# DAC_Offset.net
KiCad netlist of a schematic drawn in Altium Designer
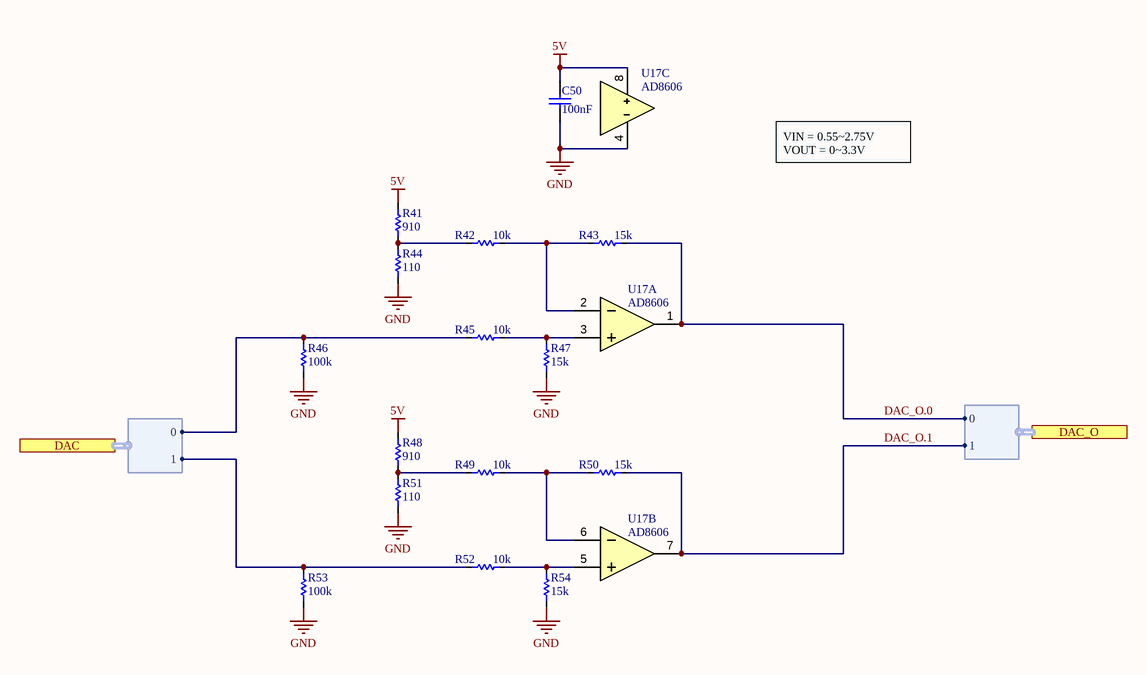
[diagram p0: DAC Offset.SchDoc]

(export (version "E")
  (design (tool "Eeschema 10.0.6"))
  (components
    (comp (ref "C50")
      (value "100nF")
      (footprint "CAP_CHIP_0603")
      (description "0603 Multilayer Ceramic Capacitors MLCC")
      (fields (field (name "TOLERANCE") "10%") (field (name "PARTNUMBER") "CC0603KRX7R9BB104"))
      (libsource (lib "Sainsbury Wellcome Centre") (part "Cap"))
    )
    (comp (ref "R41")
      (value "910")
      (footprint "RES_CHIP_0603")
      (description "100mW Thick Film Resistors 75V ±100ppm/℃ ±1% 0603 Chip Resistor")
      (fields (field (name "PARTNUMBER") "HPCR0603F910RK9") (field (name "TOLERANCE") "1%"))
      (libsource (lib "Sainsbury Wellcome Centre") (part "Res"))
    )
    (comp (ref "R42")
      (value "10k")
      (footprint "RES_CHIP_0603")
      (description "100mW Thick Film Resistors 75V ±100ppm/℃ ±1% 0603 Chip Resistor")
      (fields (field (name "PARTNUMBER") "0603WAF1002T5E") (field (name "TOLERANCE") "1%"))
      (libsource (lib "Sainsbury Wellcome Centre") (part "Res"))
    )
    (comp (ref "R43")
      (value "15k")
      (footprint "RES_CHIP_0603")
      (description "100mW Thick Film Resistors 75V ±100ppm/℃ ±1% 0603 Chip Resistor")
      (fields (field (name "PARTNUMBER") "0603WAF1502T5E") (field (name "TOLERANCE") "1%"))
      (libsource (lib "Sainsbury Wellcome Centre") (part "Res"))
    )
    (comp (ref "R44")
      (value "110")
      (footprint "RES_CHIP_0603")
      (description "100mW Thick Film Resistors 75V ±100ppm/℃ ±1% 0603 Chip Resistor")
      (fields (field (name "TOLERANCE") "1%") (field (name "PARTNUMBER") "RT0603BRD07110RL"))
      (libsource (lib "Sainsbury Wellcome Centre") (part "Res"))
    )
    (comp (ref "R45")
      (value "10k")
      (footprint "RES_CHIP_0603")
      (description "100mW Thick Film Resistors 75V ±100ppm/℃ ±1% 0603 Chip Resistor")
      (fields (field (name "PARTNUMBER") "0603WAF1002T5E") (field (name "TOLERANCE") "1%"))
      (libsource (lib "Sainsbury Wellcome Centre") (part "Res"))
    )
    (comp (ref "R46")
      (value "100k")
      (footprint "RES_CHIP_0603")
      (description "100mW Thick Film Resistors 75V ±100ppm/℃ ±1% 0603 Chip Resistor")
      (fields (field (name "PARTNUMBER") "0603WAF1003T5E") (field (name "TOLERANCE") "1%"))
      (libsource (lib "Sainsbury Wellcome Centre") (part "Res"))
    )
    (comp (ref "R47")
      (value "15k")
      (footprint "RES_CHIP_0603")
      (description "100mW Thick Film Resistors 75V ±100ppm/℃ ±1% 0603 Chip Resistor")
      (fields (field (name "PARTNUMBER") "0603WAF1502T5E") (field (name "TOLERANCE") "1%"))
      (libsource (lib "Sainsbury Wellcome Centre") (part "Res"))
    )
    (comp (ref "R48")
      (value "910")
      (footprint "RES_CHIP_0603")
      (description "100mW Thick Film Resistors 75V ±100ppm/℃ ±1% 0603 Chip Resistor")
      (fields (field (name "PARTNUMBER") "HPCR0603F910RK9") (field (name "TOLERANCE") "1%"))
      (libsource (lib "Sainsbury Wellcome Centre") (part "Res"))
    )
    (comp (ref "R49")
      (value "10k")
      (footprint "RES_CHIP_0603")
      (description "100mW Thick Film Resistors 75V ±100ppm/℃ ±1% 0603 Chip Resistor")
      (fields (field (name "PARTNUMBER") "0603WAF1002T5E") (field (name "TOLERANCE") "1%"))
      (libsource (lib "Sainsbury Wellcome Centre") (part "Res"))
    )
    (comp (ref "R50")
      (value "15k")
      (footprint "RES_CHIP_0603")
      (description "100mW Thick Film Resistors 75V ±100ppm/℃ ±1% 0603 Chip Resistor")
      (fields (field (name "PARTNUMBER") "0603WAF1502T5E") (field (name "TOLERANCE") "1%"))
      (libsource (lib "Sainsbury Wellcome Centre") (part "Res"))
    )
    (comp (ref "R51")
      (value "110")
      (footprint "RES_CHIP_0603")
      (description "100mW Thick Film Resistors 75V ±100ppm/℃ ±1% 0603 Chip Resistor")
      (fields (field (name "TOLERANCE") "1%") (field (name "PARTNUMBER") "RT0603BRD07110RL"))
      (libsource (lib "Sainsbury Wellcome Centre") (part "Res"))
    )
    (comp (ref "R52")
      (value "10k")
      (footprint "RES_CHIP_0603")
      (description "100mW Thick Film Resistors 75V ±100ppm/℃ ±1% 0603 Chip Resistor")
      (fields (field (name "PARTNUMBER") "0603WAF1002T5E") (field (name "TOLERANCE") "1%"))
      (libsource (lib "Sainsbury Wellcome Centre") (part "Res"))
    )
    (comp (ref "R53")
      (value "100k")
      (footprint "RES_CHIP_0603")
      (description "100mW Thick Film Resistors 75V ±100ppm/℃ ±1% 0603 Chip Resistor")
      (fields (field (name "PARTNUMBER") "0603WAF1003T5E") (field (name "TOLERANCE") "1%"))
      (libsource (lib "Sainsbury Wellcome Centre") (part "Res"))
    )
    (comp (ref "R54")
      (value "15k")
      (footprint "RES_CHIP_0603")
      (description "100mW Thick Film Resistors 75V ±100ppm/℃ ±1% 0603 Chip Resistor")
      (fields (field (name "PARTNUMBER") "0603WAF1502T5E") (field (name "TOLERANCE") "1%"))
      (libsource (lib "Sainsbury Wellcome Centre") (part "Res"))
    )
    (comp (ref "U17")
      (value "AD8606")
      (footprint "VSSOP8_3X3_0.65E")
      (description "Operational Amplifier, 2 Func, 750uV Offset-Max, CMOS, PDSO8")
      (fields (field (name "PARTNUMBER") "AD8606ARMZ-REEL"))
      (libsource (lib "Sainsbury Wellcome Centre") (part "OPAMP 8P"))
    )
  )
  (nets
    (net (code "3") (name "/DAC_O.0") (class "Default")
      (node (ref "R43") (pin "2") (pinfunction "2_2") (pintype "passive"))
      (node (ref "U17") (pin "1") (pinfunction "AOUT_1") (pintype "passive"))
    )
    (net (code "4") (name "/DAC_O.1") (class "Default")
      (node (ref "R50") (pin "2") (pinfunction "2_2") (pintype "passive"))
      (node (ref "U17") (pin "7") (pinfunction "BOUT_7") (pintype "passive"))
    )
    (net (code "7") (name "5V") (class "Default")
      (node (ref "C50") (pin "2") (pinfunction "2_2") (pintype "passive"))
      (node (ref "R41") (pin "2") (pinfunction "2_2") (pintype "passive"))
      (node (ref "R48") (pin "2") (pinfunction "2_2") (pintype "passive"))
      (node (ref "U17") (pin "8") (pinfunction "V+_8") (pintype "power_in"))
    )
    (net (code "8") (name "GND") (class "Default")
      (node (ref "C50") (pin "1") (pinfunction "1_1") (pintype "passive"))
      (node (ref "R44") (pin "1") (pinfunction "1_1") (pintype "passive"))
      (node (ref "R46") (pin "1") (pinfunction "1_1") (pintype "passive"))
      (node (ref "R47") (pin "1") (pinfunction "1_1") (pintype "passive"))
      (node (ref "R51") (pin "1") (pinfunction "1_1") (pintype "passive"))
      (node (ref "R53") (pin "1") (pinfunction "1_1") (pintype "passive"))
      (node (ref "R54") (pin "1") (pinfunction "1_1") (pintype "passive"))
      (node (ref "U17") (pin "4") (pinfunction "V-_4") (pintype "power_in"))
    )
    (net (code "9") (name "Net-(R41-Pad1)") (class "Default")
      (node (ref "R41") (pin "1") (pinfunction "1_1") (pintype "passive"))
      (node (ref "R42") (pin "1") (pinfunction "1_1") (pintype "passive"))
      (node (ref "R44") (pin "2") (pinfunction "2_2") (pintype "passive"))
    )
    (net (code "10") (name "Net-(R45-Pad1)") (class "Default")
      (node (ref "R45") (pin "1") (pinfunction "1_1") (pintype "passive"))
      (node (ref "R46") (pin "2") (pinfunction "2_2") (pintype "passive"))
    )
    (net (code "11") (name "Net-(R48-Pad1)") (class "Default")
      (node (ref "R48") (pin "1") (pinfunction "1_1") (pintype "passive"))
      (node (ref "R49") (pin "1") (pinfunction "1_1") (pintype "passive"))
      (node (ref "R51") (pin "2") (pinfunction "2_2") (pintype "passive"))
    )
    (net (code "12") (name "Net-(R52-Pad1)") (class "Default")
      (node (ref "R52") (pin "1") (pinfunction "1_1") (pintype "passive"))
      (node (ref "R53") (pin "2") (pinfunction "2_2") (pintype "passive"))
    )
    (net (code "13") (name "Net-(U17A-A+)") (class "Default")
      (node (ref "R45") (pin "2") (pinfunction "2_2") (pintype "passive"))
      (node (ref "R47") (pin "2") (pinfunction "2_2") (pintype "passive"))
      (node (ref "U17") (pin "3") (pinfunction "A+_3") (pintype "passive"))
    )
    (net (code "14") (name "Net-(U17A-A-)") (class "Default")
      (node (ref "R42") (pin "2") (pinfunction "2_2") (pintype "passive"))
      (node (ref "R43") (pin "1") (pinfunction "1_1") (pintype "passive"))
      (node (ref "U17") (pin "2") (pinfunction "A-_2") (pintype "passive"))
    )
    (net (code "15") (name "Net-(U17B-B+)") (class "Default")
      (node (ref "R52") (pin "2") (pinfunction "2_2") (pintype "passive"))
      (node (ref "R54") (pin "2") (pinfunction "2_2") (pintype "passive"))
      (node (ref "U17") (pin "5") (pinfunction "B+_5") (pintype "passive"))
    )
    (net (code "16") (name "Net-(U17B-B-)") (class "Default")
      (node (ref "R49") (pin "2") (pinfunction "2_2") (pintype "passive"))
      (node (ref "R50") (pin "1") (pinfunction "1_1") (pintype "passive"))
      (node (ref "U17") (pin "6") (pinfunction "B-_6") (pintype "passive"))
    )
  )
)
